# encoder.net
KiCad netlist of a schematic drawn in EAGLE
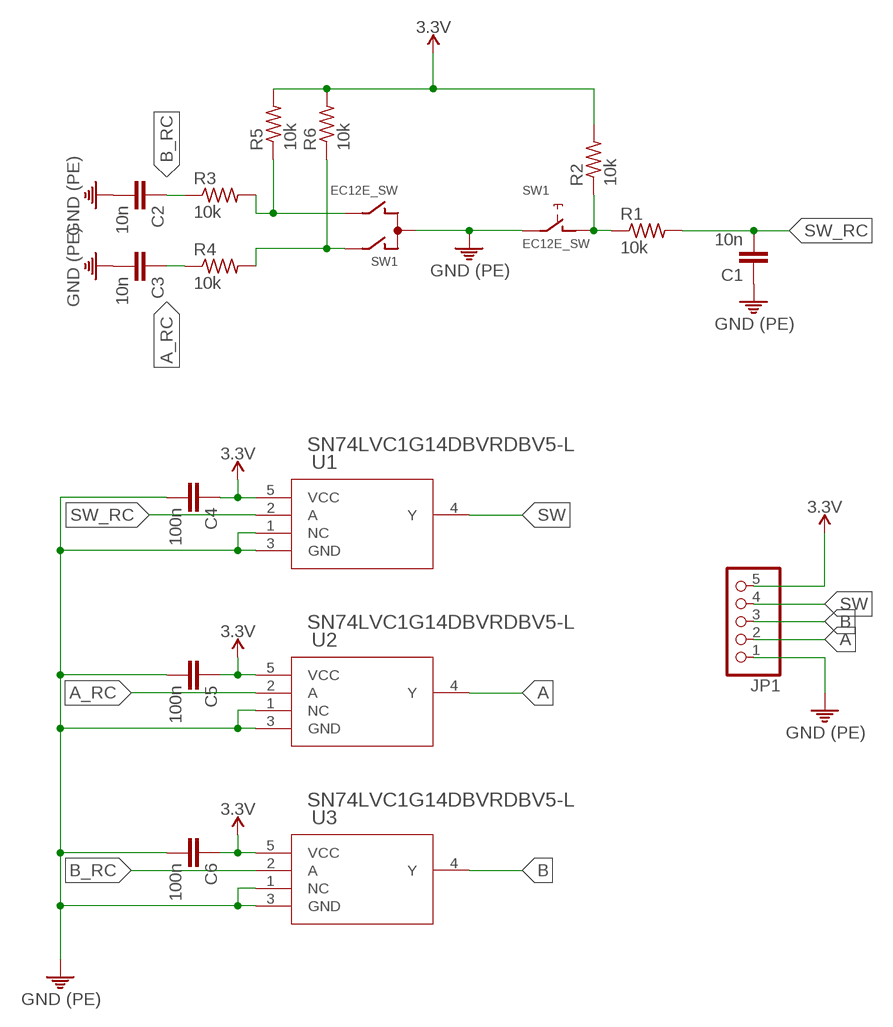
[diagram p0: schematic, sheet 1]

(export (version "E")
  (design (tool "Eeschema 10.0.6"))
  (components
    (comp (ref "C1")
      (value "10n")
      (footprint "eagle-import:C0603")
      (libsource (lib "eagle-import") (part "C-EUC0603"))
    )
    (comp (ref "C2")
      (value "10n")
      (footprint "eagle-import:C0603")
      (libsource (lib "eagle-import") (part "C-EUC0603"))
    )
    (comp (ref "C3")
      (value "10n")
      (footprint "eagle-import:C0603")
      (libsource (lib "eagle-import") (part "C-EUC0603"))
    )
    (comp (ref "C4")
      (value "100n")
      (footprint "eagle-import:C0603")
      (libsource (lib "eagle-import") (part "C-EUC0603"))
    )
    (comp (ref "C5")
      (value "100n")
      (footprint "eagle-import:C0603")
      (libsource (lib "eagle-import") (part "C-EUC0603"))
    )
    (comp (ref "C6")
      (value "100n")
      (footprint "eagle-import:C0603")
      (libsource (lib "eagle-import") (part "C-EUC0603"))
    )
    (comp (ref "JP1")
      (value "PINHD-1X5")
      (footprint "eagle-import:1X05")
      (libsource (lib "eagle-import") (part "PINHD-1X5"))
    )
    (comp (ref "R1")
      (value "10k")
      (footprint "eagle-import:R0603")
      (libsource (lib "eagle-import") (part "R-US_R0603"))
    )
    (comp (ref "R2")
      (value "10k")
      (footprint "eagle-import:R0603")
      (libsource (lib "eagle-import") (part "R-US_R0603"))
    )
    (comp (ref "R3")
      (value "10k")
      (footprint "eagle-import:R0603")
      (libsource (lib "eagle-import") (part "R-US_R0603"))
    )
    (comp (ref "R4")
      (value "10k")
      (footprint "eagle-import:R0603")
      (libsource (lib "eagle-import") (part "R-US_R0603"))
    )
    (comp (ref "R5")
      (value "10k")
      (footprint "eagle-import:R0603")
      (libsource (lib "eagle-import") (part "R-US_R0603"))
    )
    (comp (ref "R6")
      (value "10k")
      (footprint "eagle-import:R0603")
      (libsource (lib "eagle-import") (part "R-US_R0603"))
    )
    (comp (ref "SW1")
      (value "EC12E_SW")
      (footprint "eagle-import:ALPS_EC12E_SW")
      (fields (field (name "MPN") "EC12E2424407"))
      (libsource (lib "eagle-import") (part "EC12E_SW"))
    )
    (comp (ref "U1")
      (value "SN74LVC1G14DBVRDBV5-L")
      (footprint "eagle-import:DBV5-L")
      (fields
        (field (name "MANUFACTURER_PART_NUMBER") "SN74LVC1G14DBVR")
        (field (name "COPYRIGHT") "Copyright (C) 2022 Ultra Librarian. All rights reserved.")
      )
      (libsource (lib "eagle-import") (part "SN74LVC1G14DBVRDBV5-L"))
    )
    (comp (ref "U2")
      (value "SN74LVC1G14DBVRDBV5-L")
      (footprint "eagle-import:DBV5-L")
      (fields
        (field (name "MANUFACTURER_PART_NUMBER") "SN74LVC1G14DBVR")
        (field (name "COPYRIGHT") "Copyright (C) 2022 Ultra Librarian. All rights reserved.")
      )
      (libsource (lib "eagle-import") (part "SN74LVC1G14DBVRDBV5-L"))
    )
    (comp (ref "U3")
      (value "SN74LVC1G14DBVRDBV5-L")
      (footprint "eagle-import:DBV5-L")
      (fields
        (field (name "MANUFACTURER_PART_NUMBER") "SN74LVC1G14DBVR")
        (field (name "COPYRIGHT") "Copyright (C) 2022 Ultra Librarian. All rights reserved.")
      )
      (libsource (lib "eagle-import") (part "SN74LVC1G14DBVRDBV5-L"))
    )
  )
  (nets
    (net (code "1") (name "3.3V") (class "Default")
      (node (ref "C4") (pin "1") (pinfunction "1_1") (pintype "passive"))
      (node (ref "C5") (pin "1") (pinfunction "1_1") (pintype "passive"))
      (node (ref "C6") (pin "1") (pinfunction "1_1") (pintype "passive"))
      (node (ref "JP1") (pin "5") (pinfunction "5_5") (pintype "passive"))
      (node (ref "R2") (pin "2") (pinfunction "2_2") (pintype "passive"))
      (node (ref "R5") (pin "2") (pinfunction "2_2") (pintype "passive"))
      (node (ref "R6") (pin "2") (pinfunction "2_2") (pintype "passive"))
      (node (ref "U1") (pin "5") (pinfunction "VCC_5") (pintype "power_in"))
      (node (ref "U2") (pin "5") (pinfunction "VCC_5") (pintype "power_in"))
      (node (ref "U3") (pin "5") (pinfunction "VCC_5") (pintype "power_in"))
    )
    (net (code "2") (name "A") (class "Default")
      (node (ref "JP1") (pin "2") (pinfunction "2_2") (pintype "passive"))
      (node (ref "U2") (pin "4") (pinfunction "Y_4") (pintype "output"))
    )
    (net (code "3") (name "A_RC") (class "Default")
      (node (ref "C3") (pin "1") (pinfunction "1_1") (pintype "passive"))
      (node (ref "R4") (pin "1") (pinfunction "1_1") (pintype "passive"))
      (node (ref "U2") (pin "2") (pinfunction "A_2") (pintype "input"))
    )
    (net (code "4") (name "B") (class "Default")
      (node (ref "JP1") (pin "3") (pinfunction "3_3") (pintype "passive"))
      (node (ref "U3") (pin "4") (pinfunction "Y_4") (pintype "output"))
    )
    (net (code "5") (name "B_RC") (class "Default")
      (node (ref "C2") (pin "1") (pinfunction "1_1") (pintype "passive"))
      (node (ref "R3") (pin "1") (pinfunction "1_1") (pintype "passive"))
      (node (ref "U3") (pin "2") (pinfunction "A_2") (pintype "input"))
    )
    (net (code "6") (name "Net-(R3-Pad2)") (class "Default")
      (node (ref "R3") (pin "2") (pinfunction "2_2") (pintype "passive"))
      (node (ref "R5") (pin "1") (pinfunction "1_1") (pintype "passive"))
      (node (ref "SW1") (pin "B") (pinfunction "B_B") (pintype "passive"))
    )
    (net (code "7") (name "Net-(R4-Pad2)") (class "Default")
      (node (ref "R4") (pin "2") (pinfunction "2_2") (pintype "passive"))
      (node (ref "R6") (pin "1") (pinfunction "1_1") (pintype "passive"))
      (node (ref "SW1") (pin "A") (pinfunction "A_A") (pintype "passive"))
    )
    (net (code "8") (name "Net-(SW1B-1)") (class "Default")
      (node (ref "R1") (pin "1") (pinfunction "1_1") (pintype "passive"))
      (node (ref "R2") (pin "1") (pinfunction "1_1") (pintype "passive"))
      (node (ref "SW1") (pin "D") (pinfunction "1_D") (pintype "passive"))
    )
    (net (code "9") (name "POWER-GND") (class "Default")
      (node (ref "C1") (pin "1") (pinfunction "1_1") (pintype "passive"))
      (node (ref "C2") (pin "2") (pinfunction "2_2") (pintype "passive"))
      (node (ref "C3") (pin "2") (pinfunction "2_2") (pintype "passive"))
      (node (ref "C4") (pin "2") (pinfunction "2_2") (pintype "passive"))
      (node (ref "C5") (pin "2") (pinfunction "2_2") (pintype "passive"))
      (node (ref "C6") (pin "2") (pinfunction "2_2") (pintype "passive"))
      (node (ref "JP1") (pin "1") (pinfunction "1_1") (pintype "passive"))
      (node (ref "SW1") (pin "C") (pinfunction "C_C") (pintype "passive"))
      (node (ref "SW1") (pin "E") (pinfunction "2_E") (pintype "passive"))
      (node (ref "U1") (pin "1") (pinfunction "NC_1") (pintype "passive"))
      (node (ref "U1") (pin "3") (pinfunction "GND_3") (pintype "power_in"))
      (node (ref "U2") (pin "1") (pinfunction "NC_1") (pintype "passive"))
      (node (ref "U2") (pin "3") (pinfunction "GND_3") (pintype "power_in"))
      (node (ref "U3") (pin "1") (pinfunction "NC_1") (pintype "passive"))
      (node (ref "U3") (pin "3") (pinfunction "GND_3") (pintype "power_in"))
    )
    (net (code "10") (name "SW") (class "Default")
      (node (ref "JP1") (pin "4") (pinfunction "4_4") (pintype "passive"))
      (node (ref "U1") (pin "4") (pinfunction "Y_4") (pintype "output"))
    )
    (net (code "11") (name "SW_RC") (class "Default")
      (node (ref "C1") (pin "2") (pinfunction "2_2") (pintype "passive"))
      (node (ref "R1") (pin "2") (pinfunction "2_2") (pintype "passive"))
      (node (ref "U1") (pin "2") (pinfunction "A_2") (pintype "input"))
    )
  )
)
